# P19_HDMI_OUT.net
KiCad netlist of a schematic drawn in Altium Designer
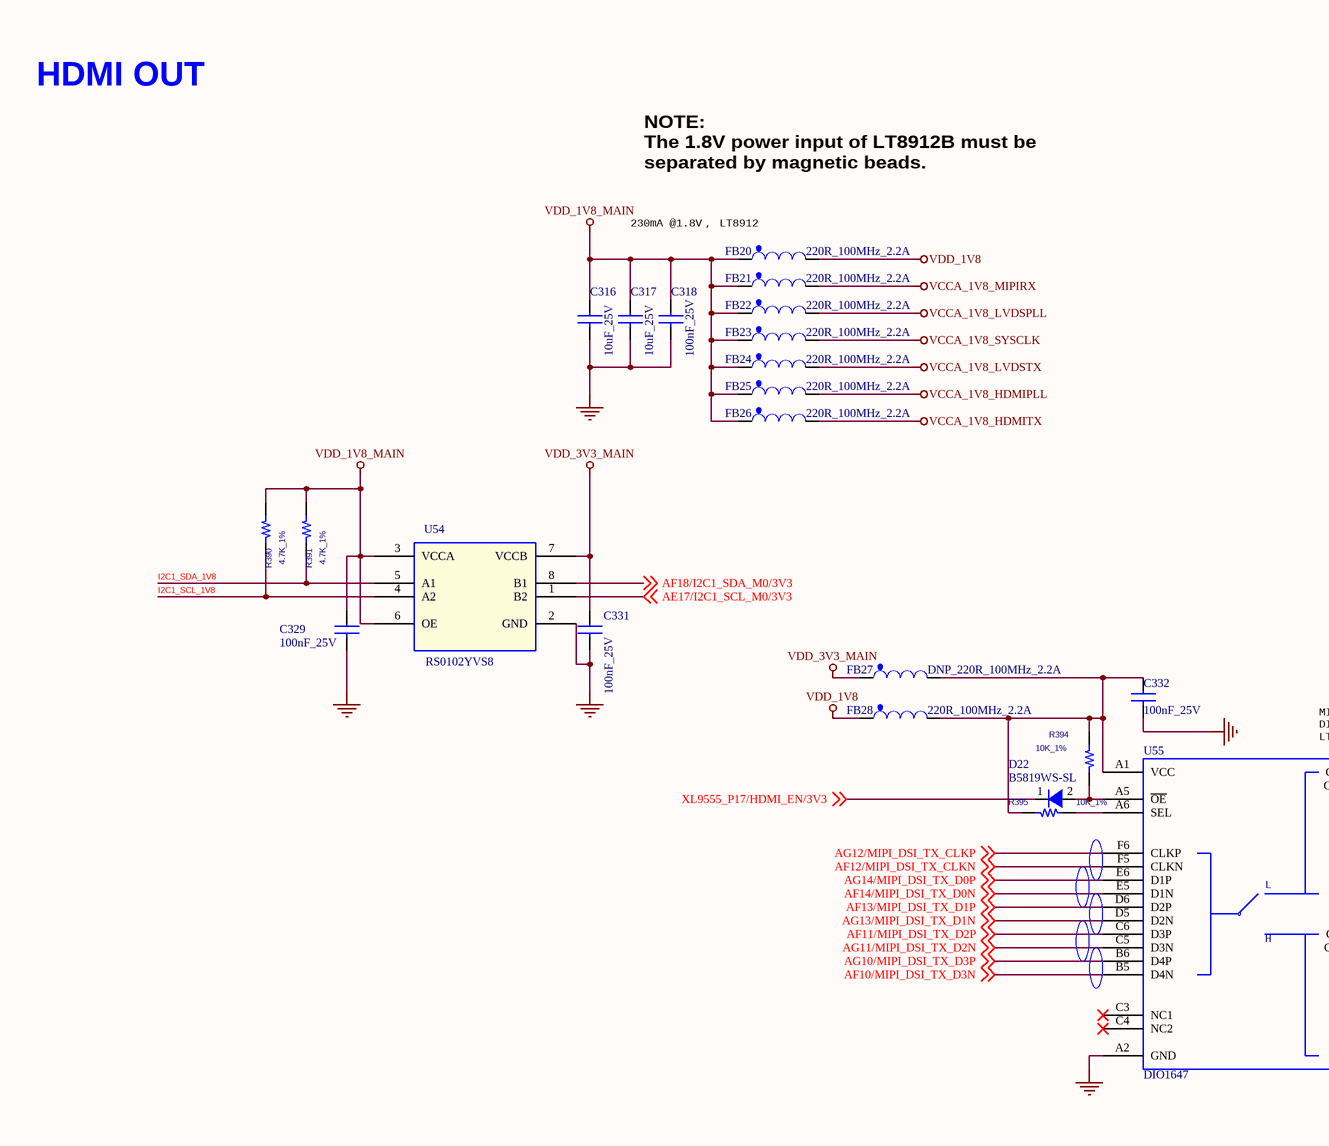
[diagram p0: P19_HDMI OUT.SchDoc, top left]
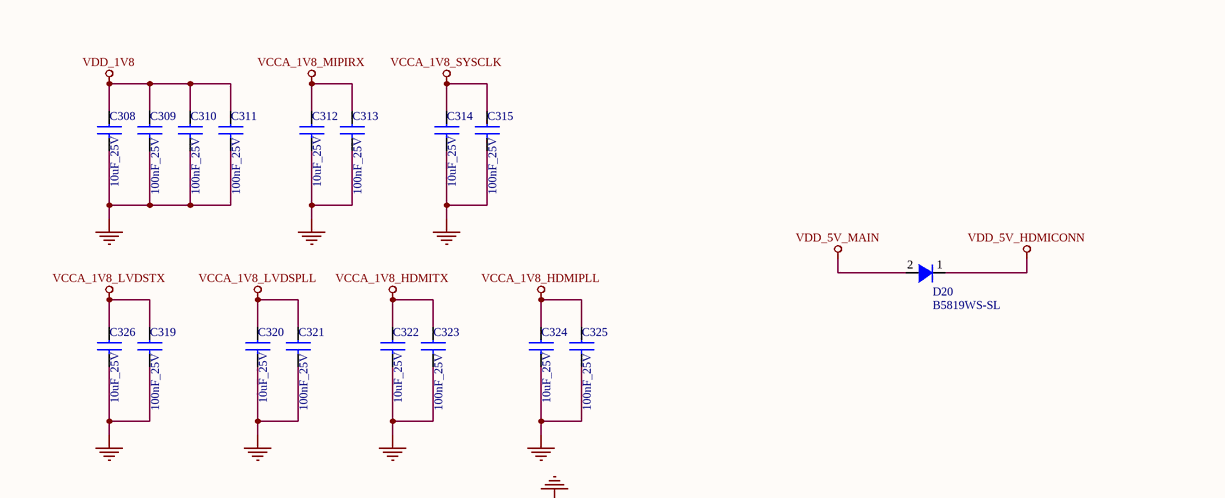
[diagram p1: P19_HDMI OUT.SchDoc, top right]
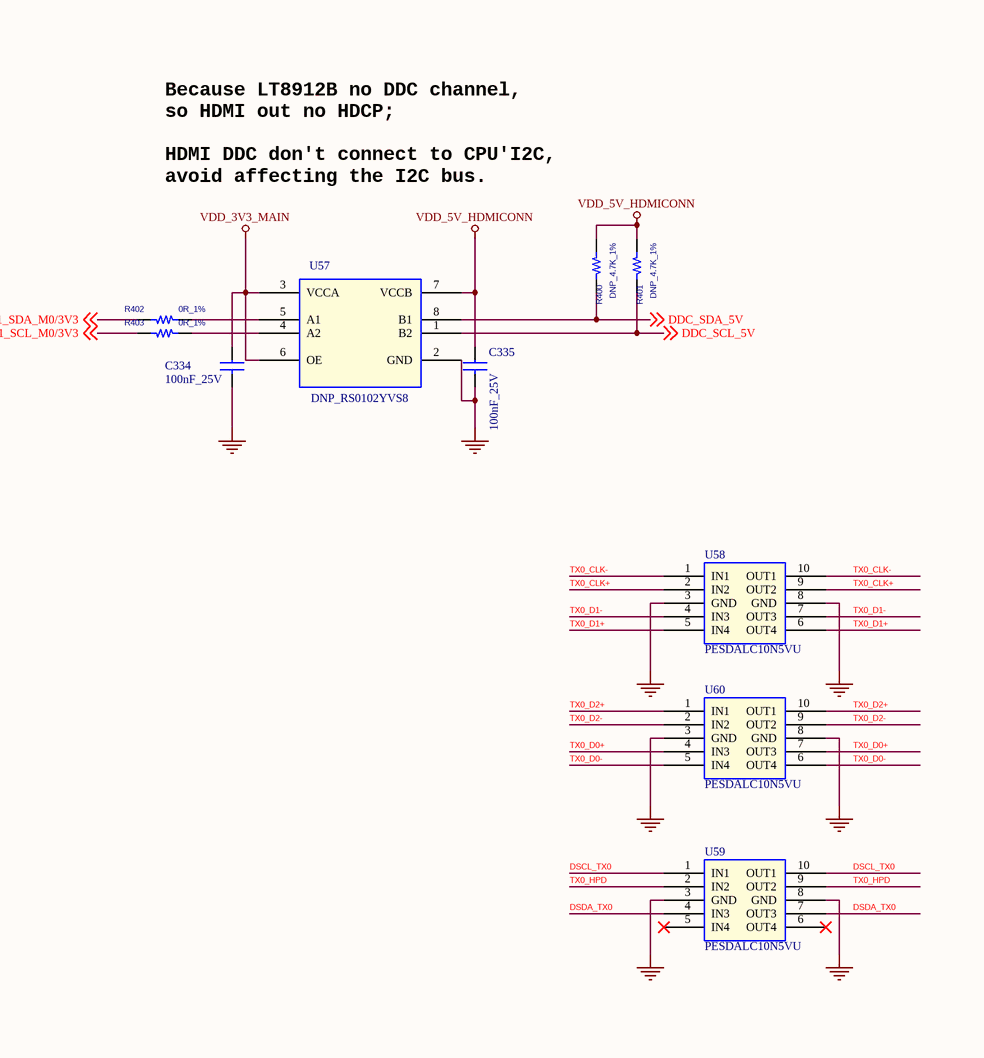
[diagram p2: P19_HDMI OUT.SchDoc, bottom left]
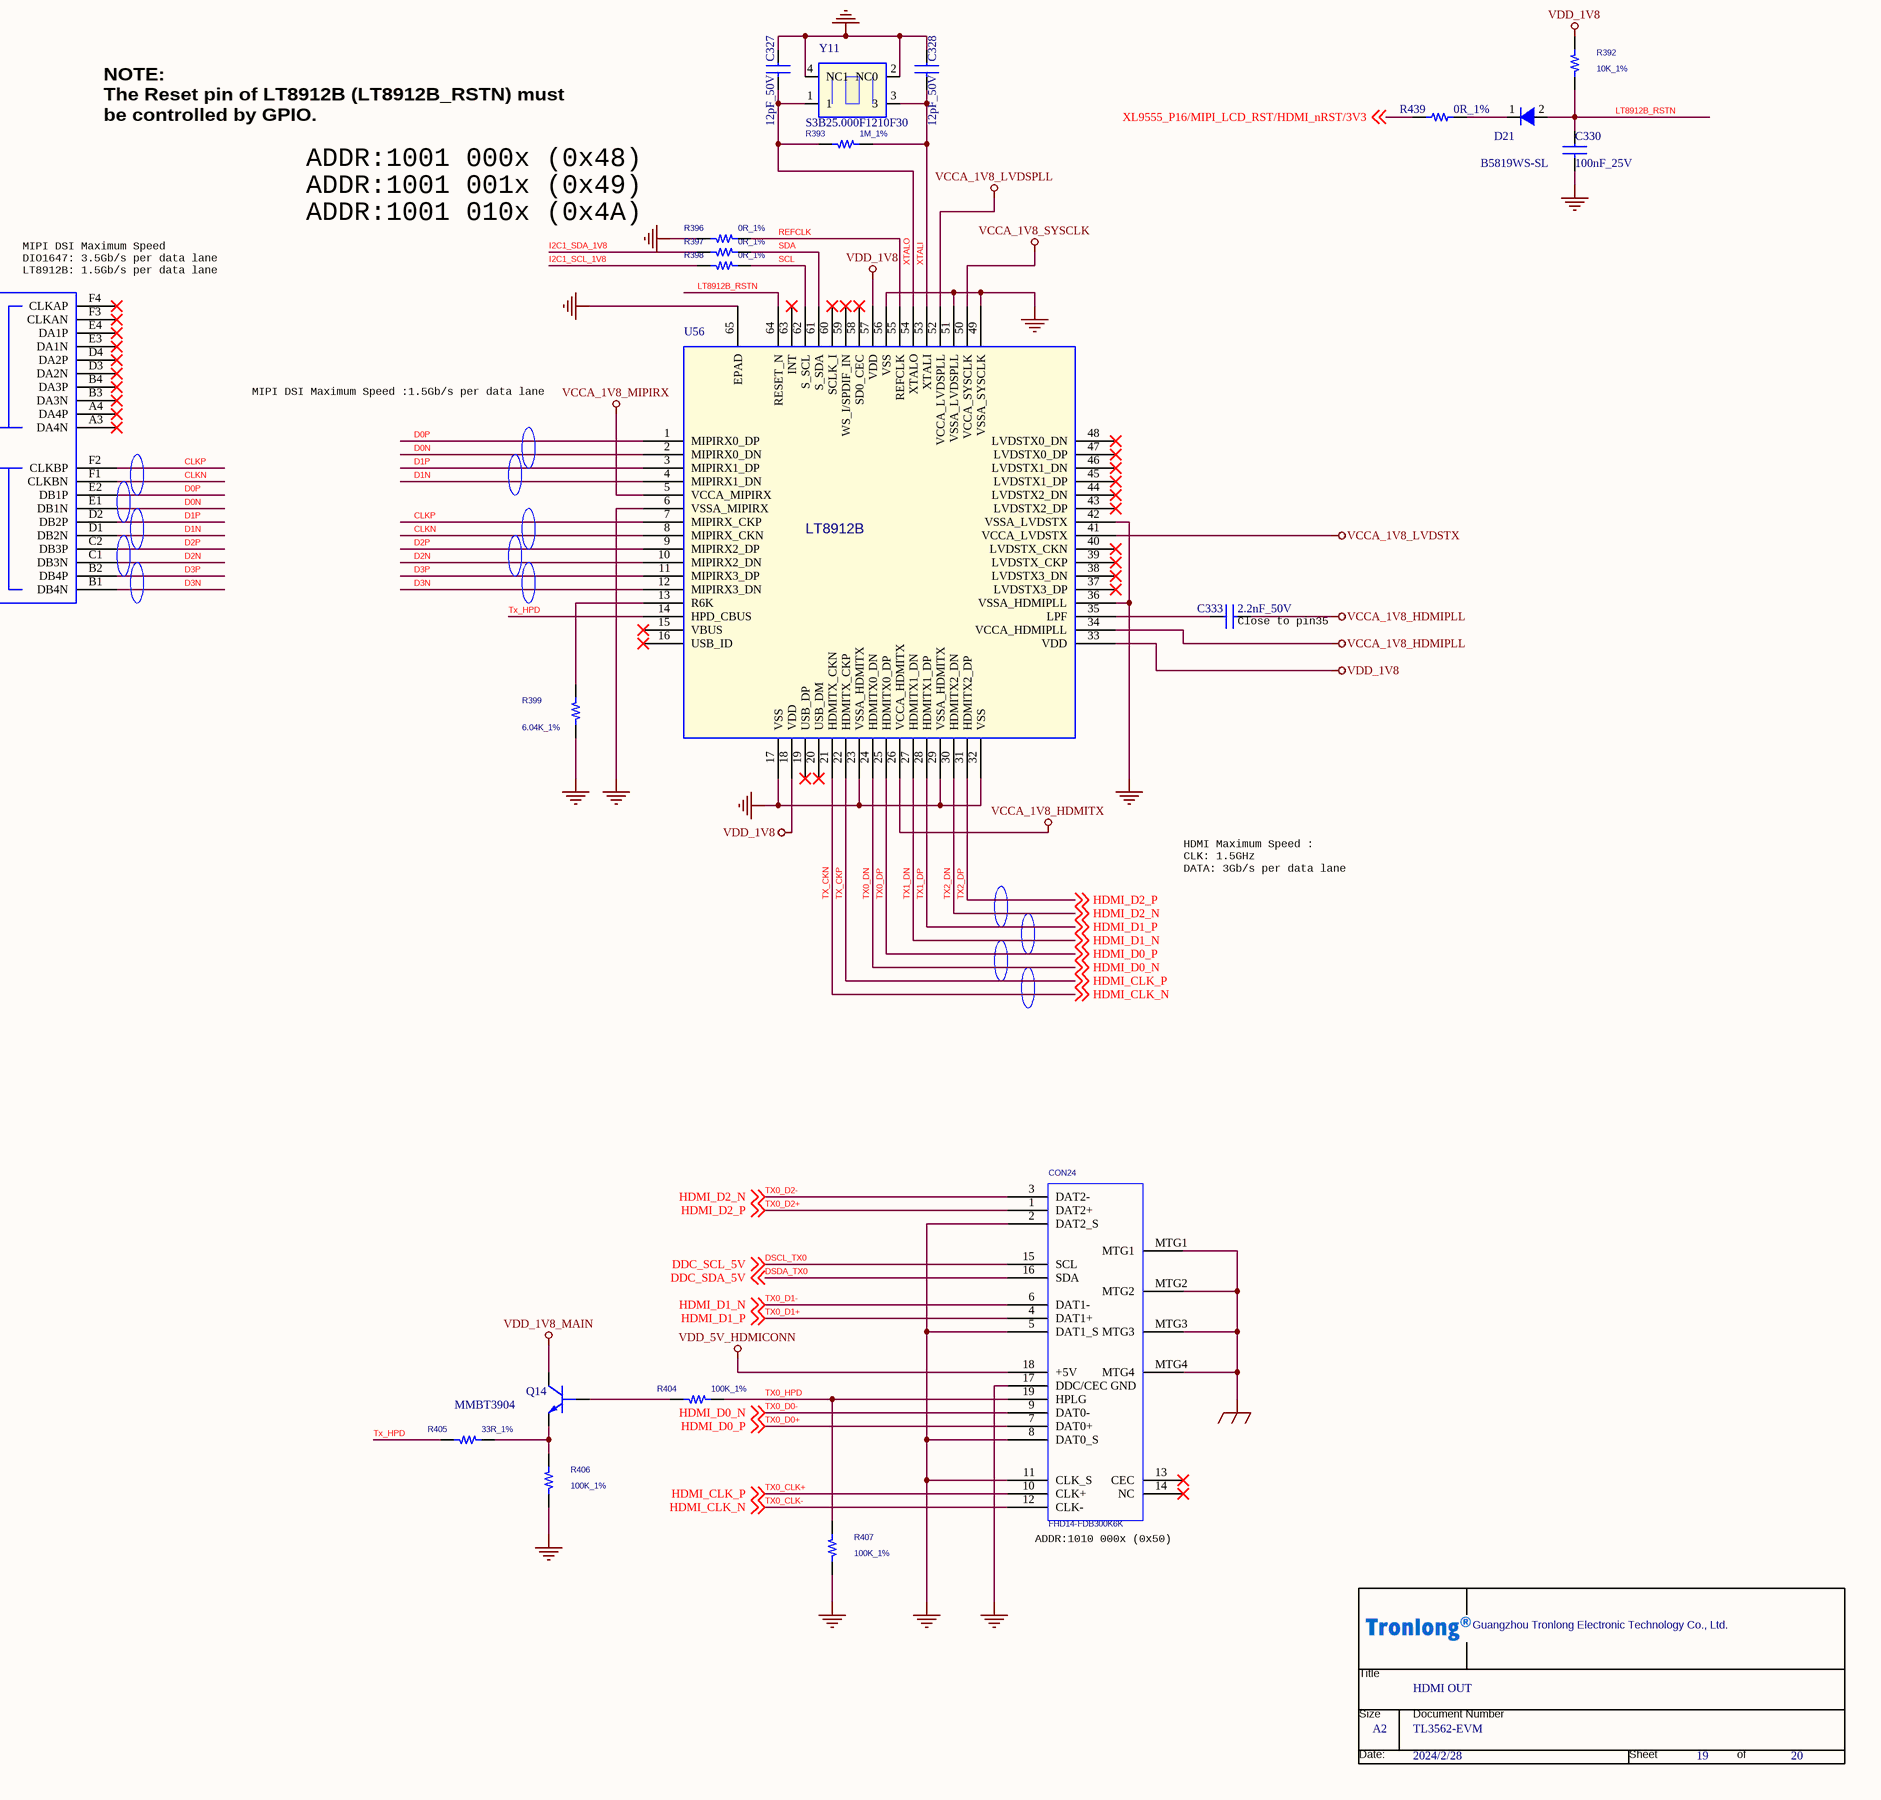
[diagram p3: P19_HDMI OUT.SchDoc, bottom right]

(export (version "E")
  (design (tool "Eeschema 10.0.6"))
  (components
    (comp (ref "C308")
      (value "10uF_25V")
      (footprint "C0603")
      (description "贴片陶瓷电容,10uF,10%,10V,X5R")
      (fields (field (name "PART NUMBER") "117-00-3043") (field (name "DESIGNER") "Hujin"))
      (libsource (lib "*") (part "CAP_NP0603"))
    )
    (comp (ref "C309")
      (value "100nF_25V")
      (footprint "C0402")
      (description "贴片陶瓷电容,100nF,10%,25V,X5R")
      (fields (field (name "PART NUMBER") "117-00-3036") (field (name "DESIGNER") "Hujin"))
      (libsource (lib "*") (part "CAP_NP0603"))
    )
    (comp (ref "C310")
      (value "100nF_25V")
      (footprint "C0402")
      (description "贴片陶瓷电容,100nF,10%,25V,X5R")
      (fields (field (name "PART NUMBER") "117-00-3036") (field (name "DESIGNER") "Hujin"))
      (libsource (lib "*") (part "CAP_NP0603"))
    )
    (comp (ref "C311")
      (value "100nF_25V")
      (footprint "C0402")
      (description "贴片陶瓷电容,100nF,10%,25V,X5R")
      (fields (field (name "PART NUMBER") "117-00-3036") (field (name "DESIGNER") "Hujin"))
      (libsource (lib "*") (part "CAP_NP0603"))
    )
    (comp (ref "C312")
      (value "10uF_25V")
      (footprint "C0603")
      (description "贴片陶瓷电容,10uF,10%,10V,X5R")
      (fields (field (name "PART NUMBER") "117-00-3043") (field (name "DESIGNER") "Hujin"))
      (libsource (lib "*") (part "CAP_NP0603"))
    )
    (comp (ref "C313")
      (value "100nF_25V")
      (footprint "C0402")
      (description "贴片陶瓷电容,100nF,10%,25V,X5R")
      (fields (field (name "PART NUMBER") "117-00-3036") (field (name "DESIGNER") "Hujin"))
      (libsource (lib "*") (part "CAP_NP0603"))
    )
    (comp (ref "C314")
      (value "10uF_25V")
      (footprint "C0603")
      (description "贴片陶瓷电容,10uF,10%,10V,X5R")
      (fields (field (name "PART NUMBER") "117-00-3043") (field (name "DESIGNER") "Hujin"))
      (libsource (lib "*") (part "CAP_NP0603"))
    )
    (comp (ref "C315")
      (value "100nF_25V")
      (footprint "C0402")
      (description "贴片陶瓷电容,100nF,10%,25V,X5R")
      (fields (field (name "PART NUMBER") "117-00-3036") (field (name "DESIGNER") "Hujin"))
      (libsource (lib "*") (part "CAP_NP0603"))
    )
    (comp (ref "C316")
      (value "10uF_25V")
      (footprint "C0603")
      (description "贴片陶瓷电容,10uF,10%,10V,X5R")
      (fields (field (name "PART NUMBER") "117-00-3043") (field (name "DESIGNER") "Hujin"))
      (libsource (lib "*") (part "CAP_NP0603"))
    )
    (comp (ref "C317")
      (value "10uF_25V")
      (footprint "C0603")
      (description "贴片陶瓷电容,10uF,10%,10V,X5R")
      (fields (field (name "PART NUMBER") "117-00-3043") (field (name "DESIGNER") "Hujin"))
      (libsource (lib "*") (part "CAP_NP0603"))
    )
    (comp (ref "C318")
      (value "100nF_25V")
      (footprint "C0402")
      (description "贴片陶瓷电容,100nF,10%,25V,X5R")
      (fields (field (name "PART NUMBER") "117-00-3036") (field (name "DESIGNER") "Hujin"))
      (libsource (lib "*") (part "CAP_NP0603"))
    )
    (comp (ref "C319")
      (value "100nF_25V")
      (footprint "C0402")
      (description "贴片陶瓷电容,100nF,10%,25V,X5R")
      (fields (field (name "PART NUMBER") "117-00-3036") (field (name "DESIGNER") "Hujin"))
      (libsource (lib "*") (part "CAP_NP0603"))
    )
    (comp (ref "C320")
      (value "10uF_25V")
      (footprint "C0603")
      (description "贴片陶瓷电容,10uF,10%,10V,X5R")
      (fields (field (name "PART NUMBER") "117-00-3043") (field (name "DESIGNER") "Hujin"))
      (libsource (lib "*") (part "CAP_NP0603"))
    )
    (comp (ref "C321")
      (value "100nF_25V")
      (footprint "C0402")
      (description "贴片陶瓷电容,100nF,10%,25V,X5R")
      (fields (field (name "PART NUMBER") "117-00-3036") (field (name "DESIGNER") "Hujin"))
      (libsource (lib "*") (part "CAP_NP0603"))
    )
    (comp (ref "C322")
      (value "10uF_25V")
      (footprint "C0603")
      (description "贴片陶瓷电容,10uF,10%,10V,X5R")
      (fields (field (name "PART NUMBER") "117-00-3043") (field (name "DESIGNER") "Hujin"))
      (libsource (lib "*") (part "CAP_NP0603"))
    )
    (comp (ref "C323")
      (value "100nF_25V")
      (footprint "C0402")
      (description "贴片陶瓷电容,100nF,10%,25V,X5R")
      (fields (field (name "PART NUMBER") "117-00-3036") (field (name "DESIGNER") "Hujin"))
      (libsource (lib "*") (part "CAP_NP0603"))
    )
    (comp (ref "C324")
      (value "10uF_25V")
      (footprint "C0603")
      (description "贴片陶瓷电容,10uF,10%,10V,X5R")
      (fields (field (name "PART NUMBER") "117-00-3043") (field (name "DESIGNER") "Hujin"))
      (libsource (lib "*") (part "CAP_NP0603"))
    )
    (comp (ref "C325")
      (value "100nF_25V")
      (footprint "C0402")
      (description "贴片陶瓷电容,100nF,10%,25V,X5R")
      (fields (field (name "PART NUMBER") "117-00-3036") (field (name "DESIGNER") "Hujin"))
      (libsource (lib "*") (part "CAP_NP0603"))
    )
    (comp (ref "C326")
      (value "10uF_25V")
      (footprint "C0603")
      (description "贴片陶瓷电容,10uF,10%,10V,X5R")
      (fields (field (name "PART NUMBER") "117-00-3043") (field (name "DESIGNER") "Hujin"))
      (libsource (lib "*") (part "CAP_NP0603"))
    )
    (comp (ref "C327")
      (value "12pF_50V")
      (footprint "C0402")
      (description "贴片陶瓷电容,12pF,5%,50V,COG")
      (fields (field (name "PART NUMBER") "117-00-3002") (field (name "DESIGNER") "Hujin"))
      (libsource (lib "*") (part "CAP_NP0603"))
    )
    (comp (ref "C328")
      (value "12pF_50V")
      (footprint "C0402")
      (description "贴片陶瓷电容,12pF,5%,50V,COG")
      (fields (field (name "PART NUMBER") "117-00-3002") (field (name "DESIGNER") "Hujin"))
      (libsource (lib "*") (part "CAP_NP0603"))
    )
    (comp (ref "C329")
      (value "100nF_25V")
      (footprint "C0402")
      (description "贴片陶瓷电容,100nF,10%,25V,X5R")
      (libsource (lib "*") (part "CAP NP_Dup3"))
    )
    (comp (ref "C330")
      (value "100nF_25V")
      (footprint "C0402")
      (description "贴片陶瓷电容,100nF,10%,25V,X5R")
      (fields (field (name "PART NUMBER") "117-00-3036") (field (name "DESIGNER") "Hujin"))
      (libsource (lib "*") (part "CAP_NP0603"))
    )
    (comp (ref "C331")
      (value "100nF_25V")
      (footprint "C0402")
      (description "贴片陶瓷电容,100nF,10%,25V,X5R")
      (libsource (lib "*") (part "CAP NP_Dup3"))
    )
    (comp (ref "C332")
      (value "100nF_25V")
      (footprint "C0402")
      (description "贴片陶瓷电容,100nF,10%,25V,X5R")
      (fields (field (name "PART NUMBER") "117-00-3036"))
      (libsource (lib "*") (part "CAP_NP"))
    )
    (comp (ref "C333")
      (value "2.2nF_50V")
      (footprint "C0603")
      (description "2.2nF,10%,C0603,50V,")
      (fields (field (name "PART NUMBER") "117-00-3023") (field (name "DESIGNER") "Hujin"))
      (libsource (lib "*") (part "CAP_NP0603"))
    )
    (comp (ref "C334")
      (value "100nF_25V")
      (footprint "C0402")
      (description "贴片陶瓷电容,100nF,10%,25V,X5R")
      (libsource (lib "*") (part "CAP NP_Dup3"))
    )
    (comp (ref "C335")
      (value "100nF_25V")
      (footprint "C0402")
      (description "贴片陶瓷电容,100nF,10%,25V,X5R")
      (libsource (lib "*") (part "CAP NP_Dup3"))
    )
    (comp (ref "CON24")
      (value "FHD14-FDB300K6K")
      (footprint "DIP_HDMI-A")
      (description "HDMI接口，19PIN，侧立，90度")
      (fields (field (name "MFR") "FCI") (field (name "TIINTPARTNUMBER") "2C0085"))
      (libsource (lib "TL3562-EVM-A1-0-000-D-20231116") (part "2C_Conn_HDMI_TypeA"))
    )
    (comp (ref "D20")
      (value "B5819WS-SL")
      (footprint "SOD-323")
      (description "肖特基二极管,VR=40V,IF=1A,VF=0.6V@1A")
      (fields (field (name "TIINTPARTNUMBER") "1E0013") (field (name "MFR") "On Semiconductor"))
      (libsource (lib "*") (part "Diode200mA250V_2"))
    )
    (comp (ref "D21")
      (value "B5819WS-SL")
      (footprint "SOD-323")
      (description "肖特基二极管,VR=40V,IF=1A,VF=0.6V@1A")
      (fields (field (name "TIINTPARTNUMBER") "1E0013") (field (name "MFR") "On Semiconductor"))
      (libsource (lib "*") (part "Diode200mA250V_2"))
    )
    (comp (ref "D22")
      (value "B5819WS-SL")
      (footprint "SOD-323")
      (description "肖特基二极管,VR=40V,IF=1A,VF=0.6V@1A")
      (fields (field (name "TIINTPARTNUMBER") "1E0013") (field (name "MFR") "On Semiconductor"))
      (libsource (lib "*") (part "Diode200mA250V_2"))
    )
    (comp (ref "FB20")
      (value "220R_100MHz_2.2A")
      (footprint "L0603")
      (description "磁珠,50mΩ,2.2A,220R@100MHz")
      (fields
        (field (name "MANUFACTURER") "深圳顺络电子股份有限公司（Sunlord）")
        (field (name "MANUFACTURER PARTNUMBER") "UPZ1608U221-2R2TF")
      )
      (libsource (lib "*") (part "FERRITE BEAD"))
    )
    (comp (ref "FB21")
      (value "220R_100MHz_2.2A")
      (footprint "L0603")
      (description "磁珠,50mΩ,2.2A,220R@100MHz")
      (fields
        (field (name "MANUFACTURER") "深圳顺络电子股份有限公司（Sunlord）")
        (field (name "MANUFACTURER PARTNUMBER") "UPZ1608U221-2R2TF")
      )
      (libsource (lib "*") (part "FERRITE BEAD"))
    )
    (comp (ref "FB22")
      (value "220R_100MHz_2.2A")
      (footprint "L0603")
      (description "磁珠,50mΩ,2.2A,220R@100MHz")
      (fields
        (field (name "MANUFACTURER") "深圳顺络电子股份有限公司（Sunlord）")
        (field (name "MANUFACTURER PARTNUMBER") "UPZ1608U221-2R2TF")
      )
      (libsource (lib "*") (part "FERRITE BEAD"))
    )
    (comp (ref "FB23")
      (value "220R_100MHz_2.2A")
      (footprint "L0603")
      (description "磁珠,50mΩ,2.2A,220R@100MHz")
      (fields
        (field (name "MANUFACTURER") "深圳顺络电子股份有限公司（Sunlord）")
        (field (name "MANUFACTURER PARTNUMBER") "UPZ1608U221-2R2TF")
      )
      (libsource (lib "*") (part "FERRITE BEAD"))
    )
    (comp (ref "FB24")
      (value "220R_100MHz_2.2A")
      (footprint "L0603")
      (description "磁珠,50mΩ,2.2A,220R@100MHz")
      (fields
        (field (name "MANUFACTURER") "深圳顺络电子股份有限公司（Sunlord）")
        (field (name "MANUFACTURER PARTNUMBER") "UPZ1608U221-2R2TF")
      )
      (libsource (lib "*") (part "FERRITE BEAD"))
    )
    (comp (ref "FB25")
      (value "220R_100MHz_2.2A")
      (footprint "L0603")
      (description "磁珠,50mΩ,2.2A,220R@100MHz")
      (fields
        (field (name "MANUFACTURER") "深圳顺络电子股份有限公司（Sunlord）")
        (field (name "MANUFACTURER PARTNUMBER") "UPZ1608U221-2R2TF")
      )
      (libsource (lib "*") (part "FERRITE BEAD"))
    )
    (comp (ref "FB26")
      (value "220R_100MHz_2.2A")
      (footprint "L0603")
      (description "磁珠,50mΩ,2.2A,220R@100MHz")
      (fields
        (field (name "MANUFACTURER") "深圳顺络电子股份有限公司（Sunlord）")
        (field (name "MANUFACTURER PARTNUMBER") "UPZ1608U221-2R2TF")
      )
      (libsource (lib "*") (part "FERRITE BEAD"))
    )
    (comp (ref "FB27")
      (value "DNP_220R_100MHz_2.2A")
      (footprint "L0603")
      (description "磁珠,50mΩ,2.2A,220R@100MHz")
      (fields
        (field (name "PART NUMBER") "647-01-3069")
        (field (name "MANUFACTURER PARTNUMBER") "UPZ1608U221-2R2TF")
      )
      (libsource (lib "*") (part "FERRITE BEAD"))
    )
    (comp (ref "FB28")
      (value "220R_100MHz_2.2A")
      (footprint "L0603")
      (description "磁珠,50mΩ,2.2A,220R@100MHz")
      (fields
        (field (name "PART NUMBER") "647-01-3069")
        (field (name "MANUFACTURER PARTNUMBER") "UPZ1608U221-2R2TF")
      )
      (libsource (lib "*") (part "FERRITE BEAD"))
    )
    (comp (ref "Q14")
      (value "MMBT3904")
      (footprint "SOT23-3_DBZ3")
      (description "BJT,NPN,Vceo=40V,Ic=200mA,fT=300MHz,PD=200mW")
      (fields (field (name "MANUFACTURER") "江苏长晶科技有限公司（JSCJ）"))
      (libsource (lib "*") (part "MMBT3904/SOT"))
    )
    (comp (ref "R390")
      (value "4.7K_1%")
      (footprint "R0402")
      (description "贴片电阻,4.7K,±1%,1/16W")
      (libsource (lib "*") (part "Resistor_Dup3"))
    )
    (comp (ref "R391")
      (value "4.7K_1%")
      (footprint "R0402")
      (description "贴片电阻,4.7K,±1%,1/16W")
      (libsource (lib "*") (part "Resistor_Dup3"))
    )
    (comp (ref "R392")
      (value "10K_1%")
      (footprint "R0402")
      (description "贴片电阻,10K,±1%,1/16W")
      (libsource (lib "*") (part "Resistor_Dup3"))
    )
    (comp (ref "R393")
      (value "1M_1%")
      (footprint "R0603")
      (description "贴片电阻,1M,±1%,1/10W")
      (libsource (lib "*") (part "Resistor_Dup3"))
    )
    (comp (ref "R394")
      (value "10K_1%")
      (footprint "R0402")
      (description "贴片电阻,10K,±1%,1/16W")
      (libsource (lib "*") (part "10_R_0"))
    )
    (comp (ref "R395")
      (value "10K_1%")
      (footprint "R0402")
      (description "贴片电阻,10K,±1%,1/16W")
      (libsource (lib "*") (part "10_R_0"))
    )
    (comp (ref "R396")
      (value "0R_1%")
      (footprint "R0402")
      (description "0R,±1%,R0402,≥1/16W")
      (libsource (lib "*") (part "Resistor_Dup3"))
    )
    (comp (ref "R397")
      (value "0R_1%")
      (footprint "R0402")
      (description "0R,±1%,R0402,≥1/16W")
      (libsource (lib "*") (part "Resistor_Dup3"))
    )
    (comp (ref "R398")
      (value "0R_1%")
      (footprint "R0402")
      (description "0R,±1%,R0402,≥1/16W")
      (libsource (lib "*") (part "Resistor_Dup3"))
    )
    (comp (ref "R399")
      (value "6.04K_1%")
      (footprint "R0402")
      (description "贴片电阻,6.04K,±1%,1/16W")
      (libsource (lib "*") (part "Resistor_Dup3"))
    )
    (comp (ref "R400")
      (value "DNP_4.7K_1%")
      (footprint "R0402")
      (description "贴片电阻,4.7K,±1%,1/16W")
      (libsource (lib "*") (part "Resistor_Dup3"))
    )
    (comp (ref "R401")
      (value "DNP_4.7K_1%")
      (footprint "R0402")
      (description "贴片电阻,4.7K,±1%,1/16W")
      (libsource (lib "*") (part "Resistor_Dup3"))
    )
    (comp (ref "R402")
      (value "0R_1%")
      (footprint "R0402")
      (description "0R,±1%,R0402,≥1/16W")
      (libsource (lib "*") (part "Resistor_Dup3"))
    )
    (comp (ref "R403")
      (value "0R_1%")
      (footprint "R0402")
      (description "0R,±1%,R0402,≥1/16W")
      (libsource (lib "*") (part "Resistor_Dup3"))
    )
    (comp (ref "R404")
      (value "100K_1%")
      (footprint "R0402")
      (description "贴片电阻,100K,±1%,1/16W")
      (libsource (lib "*") (part "Resistor_Dup3"))
    )
    (comp (ref "R405")
      (value "33R_1%")
      (footprint "R0402")
      (description "贴片电阻,33R,±1%,1/16W")
      (libsource (lib "*") (part "Resistor_Dup3"))
    )
    (comp (ref "R406")
      (value "100K_1%")
      (footprint "R0402")
      (description "贴片电阻,100K,±1%,1/16W")
      (libsource (lib "*") (part "Resistor_Dup3"))
    )
    (comp (ref "R407")
      (value "100K_1%")
      (footprint "R0402")
      (description "贴片电阻,100K,±1%,1/16W")
      (libsource (lib "*") (part "Resistor_Dup3"))
    )
    (comp (ref "R439")
      (value "0R_1%")
      (footprint "R0402")
      (description "0R,±1%,R0402,≥1/16W")
      (libsource (lib "*") (part "Resistor_Dup3"))
    )
    (comp (ref "U54")
      (value "RS0102YVS8")
      (footprint "SOP8-20-91")
      (description "2位双向电平转换器")
      (fields (field (name "MANUFACTURER") "江苏润石科技有限公司（RUNIC）"))
      (libsource (lib "*") (part "TXS0102DCUR"))
    )
    (comp (ref "U55")
      (value "DIO1647")
      (footprint "WLCSP-36-0d4mm")
      (description "3.5GHz, 十单刀双掷MIPI 开关")
      (fields
        (field (name "MANUFACTURER PARTNUMBER") "DIO1647WL36")
        (field (name "MANUFACTURER") "江苏帝奥微电子股份有限公司")
      )
      (libsource (lib "TL3562-EVM-A1-0-000-D-20231116") (part "DIO1647_0"))
    )
    (comp (ref "U56")
      (value "LT8912B")
      (footprint "QFN64_LT8912B")
      (description "MIPI转HDMI/LVDS")
      (fields (field (name "MANUFACTURER") "龙迅半导体（合肥）股份有限公司") (field (name "PART NUMBER") "566-00-3037"))
      (libsource (lib "*") (part "LT8912B_QFN64_0"))
    )
    (comp (ref "U57")
      (value "DNP_RS0102YVS8")
      (footprint "SOP8-20-91")
      (description "2位双向电平转换器")
      (fields
        (field (name "MANUFACTURER PARTNUMBER") "RS0102YVS8")
        (field (name "MANUFACTURER") "江苏润石科技有限公司（RUNIC）")
      )
      (libsource (lib "*") (part "TXS0102DCUR"))
    )
    (comp (ref "U58")
      (value "PESDALC10N5VU")
      (footprint "DFN-10-2510")
      (description "4通道超低电容瞬态抑制器")
      (fields (field (name "MANUFACTURER") "上海芯导电子科技有限公司（Prisemi）"))
      (libsource (lib "*") (part "RCLAMP0524P"))
    )
    (comp (ref "U59")
      (value "PESDALC10N5VU")
      (footprint "DFN-10-2510")
      (description "4通道超低电容瞬态抑制器")
      (fields (field (name "MANUFACTURER") "上海芯导电子科技有限公司（Prisemi）"))
      (libsource (lib "*") (part "RCLAMP0524P"))
    )
    (comp (ref "U60")
      (value "PESDALC10N5VU")
      (footprint "DFN-10-2510")
      (description "4通道超低电容瞬态抑制器")
      (fields (field (name "MANUFACTURER") "上海芯导电子科技有限公司（Prisemi）"))
      (libsource (lib "*") (part "RCLAMP0524P"))
    )
    (comp (ref "Y11")
      (value "S3B25.000F1210F30")
      (footprint "SMD_3225")
      (description "四脚无源晶振,25MHz,±10ppm,12pF,30Ω,±30ppm")
      (fields (field (name "MANUFACTURER") "深圳市星通时频电子有限公司公司（JSCJ）"))
      (libsource (lib "*") (part "CRYS-4PIN"))
    )
  )
  (nets
    (net (code "1") (name "/CLKN") (class "Default")
      (node (ref "U55") (pin "F1") (pinfunction "CLKBN_F1") (pintype "passive"))
      (node (ref "U56") (pin "8") (pinfunction "MIPIRX_CKN_8") (pintype "passive"))
    )
    (net (code "2") (name "/CLKP") (class "Default")
      (node (ref "U55") (pin "F2") (pinfunction "CLKBP_F2") (pintype "passive"))
      (node (ref "U56") (pin "7") (pinfunction "MIPIRX_CKP_7") (pintype "passive"))
    )
    (net (code "3") (name "/D0N") (class "Default")
      (node (ref "U55") (pin "E1") (pinfunction "DB1N_E1") (pintype "passive"))
      (node (ref "U56") (pin "2") (pinfunction "MIPIRX0_DN_2") (pintype "passive"))
    )
    (net (code "4") (name "/D0P") (class "Default")
      (node (ref "U55") (pin "E2") (pinfunction "DB1P_E2") (pintype "passive"))
      (node (ref "U56") (pin "1") (pinfunction "MIPIRX0_DP_1") (pintype "passive"))
    )
    (net (code "5") (name "/D1N") (class "Default")
      (node (ref "U55") (pin "D1") (pinfunction "DB2N_D1") (pintype "passive"))
      (node (ref "U56") (pin "4") (pinfunction "MIPIRX1_DN_4") (pintype "passive"))
    )
    (net (code "6") (name "/D1P") (class "Default")
      (node (ref "U55") (pin "D2") (pinfunction "DB2P_D2") (pintype "passive"))
      (node (ref "U56") (pin "3") (pinfunction "MIPIRX1_DP_3") (pintype "passive"))
    )
    (net (code "7") (name "/D2N") (class "Default")
      (node (ref "U55") (pin "C1") (pinfunction "DB3N_C1") (pintype "passive"))
      (node (ref "U56") (pin "10") (pinfunction "MIPIRX2_DN_10") (pintype "passive"))
    )
    (net (code "8") (name "/D2P") (class "Default")
      (node (ref "U55") (pin "C2") (pinfunction "DB3P_C2") (pintype "passive"))
      (node (ref "U56") (pin "9") (pinfunction "MIPIRX2_DP_9") (pintype "passive"))
    )
    (net (code "9") (name "/D3N") (class "Default")
      (node (ref "U55") (pin "B1") (pinfunction "DB4N_B1") (pintype "passive"))
      (node (ref "U56") (pin "12") (pinfunction "MIPIRX3_DN_12") (pintype "passive"))
    )
    (net (code "10") (name "/D3P") (class "Default")
      (node (ref "U55") (pin "B2") (pinfunction "DB4P_B2") (pintype "passive"))
      (node (ref "U56") (pin "11") (pinfunction "MIPIRX3_DP_11") (pintype "passive"))
    )
    (net (code "11") (name "/I2C1_SCL_1V8") (class "Default")
      (node (ref "R390") (pin "1") (pinfunction "1_1") (pintype "passive"))
      (node (ref "R398") (pin "1") (pinfunction "1_1") (pintype "passive"))
      (node (ref "U54") (pin "4") (pinfunction "A2_4") (pintype "passive"))
    )
    (net (code "12") (name "/I2C1_SDA_1V8") (class "Default")
      (node (ref "R391") (pin "1") (pinfunction "1_1") (pintype "passive"))
      (node (ref "R397") (pin "1") (pinfunction "1_1") (pintype "passive"))
      (node (ref "U54") (pin "5") (pinfunction "A1_5") (pintype "passive"))
    )
    (net (code "13") (name "/LT8912B_RSTN") (class "Default")
      (node (ref "C330") (pin "1") (pinfunction "1_1") (pintype "passive"))
      (node (ref "D21") (pin "2") (pinfunction "Cathode_2") (pintype "passive"))
      (node (ref "R392") (pin "1") (pinfunction "1_1") (pintype "passive"))
      (node (ref "U56") (pin "64") (pinfunction "RESET_N_64") (pintype "passive"))
    )
    (net (code "14") (name "/REFCLK") (class "Default")
      (node (ref "R396") (pin "2") (pinfunction "2_2") (pintype "passive"))
      (node (ref "U56") (pin "55") (pinfunction "REFCLK_55") (pintype "passive"))
    )
    (net (code "15") (name "/SCL") (class "Default")
      (node (ref "R398") (pin "2") (pinfunction "2_2") (pintype "passive"))
      (node (ref "U56") (pin "62") (pinfunction "S_SCL_62") (pintype "passive"))
    )
    (net (code "16") (name "/SDA") (class "Default")
      (node (ref "R397") (pin "2") (pinfunction "2_2") (pintype "passive"))
      (node (ref "U56") (pin "61") (pinfunction "S_SDA_61") (pintype "passive"))
    )
    (net (code "17") (name "/TX0_HPD") (class "Default")
      (node (ref "CON24") (pin "19") (pinfunction "HPLG_19") (pintype "passive"))
      (node (ref "R404") (pin "1") (pinfunction "1_1") (pintype "passive"))
      (node (ref "R407") (pin "2") (pinfunction "2_2") (pintype "passive"))
      (node (ref "U59") (pin "2") (pinfunction "IN2_2") (pintype "passive"))
      (node (ref "U59") (pin "9") (pinfunction "OUT2_9") (pintype "passive"))
    )
    (net (code "18") (name "/Tx_HPD") (class "Default")
      (node (ref "R405") (pin "2") (pinfunction "2_2") (pintype "passive"))
      (node (ref "U56") (pin "14") (pinfunction "HPD_CBUS_14") (pintype "passive"))
    )
    (net (code "19") (name "/XTALI") (class "Default")
      (node (ref "C328") (pin "2") (pinfunction "2_2") (pintype "passive"))
      (node (ref "R393") (pin "1") (pinfunction "1_1") (pintype "passive"))
      (node (ref "U56") (pin "53") (pinfunction "XTALI_53") (pintype "passive"))
      (node (ref "Y11") (pin "3") (pinfunction "3_3") (pintype "passive"))
    )
    (net (code "20") (name "/XTALO") (class "Default")
      (node (ref "C327") (pin "2") (pinfunction "2_2") (pintype "passive"))
      (node (ref "R393") (pin "2") (pinfunction "2_2") (pintype "passive"))
      (node (ref "U56") (pin "54") (pinfunction "XTALO_54") (pintype "passive"))
      (node (ref "Y11") (pin "1") (pinfunction "1_1") (pintype "passive"))
    )
    (net (code "21") (name "AE17{slash}I2C1_SCL_M0{slash}3V3") (class "Default")
      (node (ref "R403") (pin "2") (pinfunction "2_2") (pintype "passive"))
      (node (ref "U54") (pin "1") (pinfunction "B2_1") (pintype "passive"))
    )
    (net (code "22") (name "AF10{slash}MIPI_DSI_TX_D3N") (class "Default")
      (node (ref "U55") (pin "B5") (pinfunction "D4N_B5") (pintype "passive"))
    )
    (net (code "23") (name "AF11{slash}MIPI_DSI_TX_D2P") (class "Default")
      (node (ref "U55") (pin "C6") (pinfunction "D3P_C6") (pintype "passive"))
    )
    (net (code "24") (name "AF12{slash}MIPI_DSI_TX_CLKN") (class "Default")
      (node (ref "U55") (pin "F5") (pinfunction "CLKN_F5") (pintype "passive"))
    )
    (net (code "25") (name "AF13{slash}MIPI_DSI_TX_D1P") (class "Default")
      (node (ref "U55") (pin "D6") (pinfunction "D2P_D6") (pintype "passive"))
    )
    (net (code "26") (name "AF14{slash}MIPI_DSI_TX_D0N") (class "Default")
      (node (ref "U55") (pin "E5") (pinfunction "D1N_E5") (pintype "passive"))
    )
    (net (code "27") (name "AF18{slash}I2C1_SDA_M0{slash}3V3") (class "Default")
      (node (ref "R402") (pin "2") (pinfunction "2_2") (pintype "passive"))
      (node (ref "U54") (pin "8") (pinfunction "B1_8") (pintype "passive"))
    )
    (net (code "28") (name "AG10{slash}MIPI_DSI_TX_D3P") (class "Default")
      (node (ref "U55") (pin "B6") (pinfunction "D4P_B6") (pintype "passive"))
    )
    (net (code "29") (name "AG11{slash}MIPI_DSI_TX_D2N") (class "Default")
      (node (ref "U55") (pin "C5") (pinfunction "D3N_C5") (pintype "passive"))
    )
    (net (code "30") (name "AG12{slash}MIPI_DSI_TX_CLKP") (class "Default")
      (node (ref "U55") (pin "F6") (pinfunction "CLKP_F6") (pintype "passive"))
    )
    (net (code "31") (name "AG13{slash}MIPI_DSI_TX_D1N") (class "Default")
      (node (ref "U55") (pin "D5") (pinfunction "D2N_D5") (pintype "passive"))
    )
    (net (code "32") (name "AG14{slash}MIPI_DSI_TX_D0P") (class "Default")
      (node (ref "U55") (pin "E6") (pinfunction "D1P_E6") (pintype "passive"))
    )
    (net (code "33") (name "DDC_SCL_5V") (class "Default")
      (node (ref "CON24") (pin "15") (pinfunction "SCL_15") (pintype "passive"))
      (node (ref "R401") (pin "1") (pinfunction "1_1") (pintype "passive"))
      (node (ref "U57") (pin "1") (pinfunction "B2_1") (pintype "passive"))
      (node (ref "U59") (pin "1") (pinfunction "IN1_1") (pintype "passive"))
      (node (ref "U59") (pin "10") (pinfunction "OUT1_10") (pintype "passive"))
    )
    (net (code "34") (name "DDC_SDA_5V") (class "Default")
      (node (ref "CON24") (pin "16") (pinfunction "SDA_16") (pintype "passive"))
      (node (ref "R400") (pin "1") (pinfunction "1_1") (pintype "passive"))
      (node (ref "U57") (pin "8") (pinfunction "B1_8") (pintype "passive"))
      (node (ref "U59") (pin "4") (pinfunction "IN3_4") (pintype "passive"))
      (node (ref "U59") (pin "7") (pinfunction "OUT3_7") (pintype "passive"))
    )
    (net (code "35") (name "EGND") (class "Default")
      (node (ref "CON24") (pin "MTG1") (pinfunction "MTG1_MTG1") (pintype "power_in"))
      (node (ref "CON24") (pin "MTG2") (pinfunction "MTG2_MTG2") (pintype "power_in"))
      (node (ref "CON24") (pin "MTG3") (pinfunction "MTG3_MTG3") (pintype "power_in"))
      (node (ref "CON24") (pin "MTG4") (pinfunction "MTG4_MTG4") (pintype "power_in"))
    )
    (net (code "36") (name "GND") (class "Default")
      (node (ref "C308") (pin "2") (pinfunction "2_2") (pintype "passive"))
      (node (ref "C309") (pin "2") (pinfunction "2_2") (pintype "passive"))
      (node (ref "C310") (pin "2") (pinfunction "2_2") (pintype "passive"))
      (node (ref "C311") (pin "2") (pinfunction "2_2") (pintype "passive"))
      (node (ref "C312") (pin "2") (pinfunction "2_2") (pintype "passive"))
      (node (ref "C313") (pin "2") (pinfunction "2_2") (pintype "passive"))
      (node (ref "C314") (pin "2") (pinfunction "2_2") (pintype "passive"))
      (node (ref "C315") (pin "2") (pinfunction "2_2") (pintype "passive"))
      (node (ref "C316") (pin "2") (pinfunction "2_2") (pintype "passive"))
      (node (ref "C317") (pin "2") (pinfunction "2_2") (pintype "passive"))
      (node (ref "C318") (pin "2") (pinfunction "2_2") (pintype "passive"))
      (node (ref "C319") (pin "2") (pinfunction "2_2") (pintype "passive"))
      (node (ref "C320") (pin "2") (pinfunction "2_2") (pintype "passive"))
      (node (ref "C321") (pin "2") (pinfunction "2_2") (pintype "passive"))
      (node (ref "C322") (pin "2") (pinfunction "2_2") (pintype "passive"))
      (node (ref "C323") (pin "2") (pinfunction "2_2") (pintype "passive"))
      (node (ref "C324") (pin "2") (pinfunction "2_2") (pintype "passive"))
      (node (ref "C325") (pin "2") (pinfunction "2_2") (pintype "passive"))
      (node (ref "C326") (pin "2") (pinfunction "2_2") (pintype "passive"))
      (node (ref "C327") (pin "1") (pinfunction "1_1") (pintype "passive"))
      (node (ref "C328") (pin "1") (pinfunction "1_1") (pintype "passive"))
      (node (ref "C329") (pin "2") (pinfunction "2_2") (pintype "passive"))
      (node (ref "C330") (pin "2") (pinfunction "2_2") (pintype "passive"))
      (node (ref "C331") (pin "2") (pinfunction "2_2") (pintype "passive"))
      (node (ref "C332") (pin "2") (pinfunction "2_2") (pintype "passive"))
      (node (ref "C334") (pin "2") (pinfunction "2_2") (pintype "passive"))
      (node (ref "C335") (pin "2") (pinfunction "2_2") (pintype "passive"))
      (node (ref "CON24") (pin "11") (pinfunction "CLK_S_11") (pintype "passive"))
      (node (ref "CON24") (pin "17") (pinfunction "DDC/CEC_GND_17") (pintype "passive"))
      (node (ref "CON24") (pin "2") (pinfunction "DAT2_S_2") (pintype "passive"))
      (node (ref "CON24") (pin "5") (pinfunction "DAT1_S_5") (pintype "passive"))
      (node (ref "CON24") (pin "8") (pinfunction "DAT0_S_8") (pintype "passive"))
      (node (ref "R396") (pin "1") (pinfunction "1_1") (pintype "passive"))
      (node (ref "R399") (pin "1") (pinfunction "1_1") (pintype "passive"))
      (node (ref "R406") (pin "1") (pinfunction "1_1") (pintype "passive"))
      (node (ref "R407") (pin "1") (pinfunction "1_1") (pintype "passive"))
      (node (ref "U54") (pin "2") (pinfunction "GND_2") (pintype "passive"))
      (node (ref "U55") (pin "A2") (pinfunction "GND_A2") (pintype "power_in"))
      (node (ref "U56") (pin "17") (pinfunction "VSS_17") (pintype "power_in"))
      (node (ref "U56") (pin "23") (pinfunction "VSSA_HDMITX_23") (pintype "power_in"))
      (node (ref "U56") (pin "29") (pinfunction "VSSA_HDMITX_29") (pintype "power_in"))
      (node (ref "U56") (pin "32") (pinfunction "VSS_32") (pintype "power_in"))
      (node (ref "U56") (pin "36") (pinfunction "VSSA_HDMIPLL_36") (pintype "power_in"))
      (node (ref "U56") (pin "42") (pinfunction "VSSA_LVDSTX_42") (pintype "power_in"))
      (node (ref "U56") (pin "49") (pinfunction "VSSA_SYSCLK_49") (pintype "power_in"))
      (node (ref "U56") (pin "51") (pinfunction "VSSA_LVDSPLL_51") (pintype "power_in"))
      (node (ref "U56") (pin "56") (pinfunction "VSS_56") (pintype "power_in"))
      (node (ref "U56") (pin "6") (pinfunction "VSSA_MIPIRX_6") (pintype "power_in"))
      (node (ref "U56") (pin "65") (pinfunction "EPAD_65") (pintype "passive"))
      (node (ref "U57") (pin "2") (pinfunction "GND_2") (pintype "passive"))
      (node (ref "U58") (pin "3") (pinfunction "GND_3") (pintype "power_in"))
      (node (ref "U58") (pin "8") (pinfunction "GND_8") (pintype "power_in"))
      (node (ref "U59") (pin "3") (pinfunction "GND_3") (pintype "power_in"))
      (node (ref "U59") (pin "8") (pinfunction "GND_8") (pintype "power_in"))
      (node (ref "U60") (pin "3") (pinfunction "GND_3") (pintype "power_in"))
      (node (ref "U60") (pin "8") (pinfunction "GND_8") (pintype "power_in"))
      (node (ref "Y11") (pin "2") (pinfunction "NC0_2") (pintype "passive"))
      (node (ref "Y11") (pin "4") (pinfunction "NC1_4") (pintype "passive"))
    )
    (net (code "37") (name "HDMI_CLK_N") (class "Default")
      (node (ref "CON24") (pin "12") (pinfunction "CLK-_12") (pintype "passive"))
      (node (ref "U56") (pin "21") (pinfunction "HDMITX_CKN_21") (pintype "passive"))
      (node (ref "U58") (pin "1") (pinfunction "IN1_1") (pintype "passive"))
      (node (ref "U58") (pin "10") (pinfunction "OUT1_10") (pintype "passive"))
    )
    (net (code "38") (name "HDMI_CLK_P") (class "Default")
      (node (ref "CON24") (pin "10") (pinfunction "CLK+_10") (pintype "passive"))
      (node (ref "U56") (pin "22") (pinfunction "HDMITX_CKP_22") (pintype "passive"))
      (node (ref "U58") (pin "2") (pinfunction "IN2_2") (pintype "passive"))
      (node (ref "U58") (pin "9") (pinfunction "OUT2_9") (pintype "passive"))
    )
    (net (code "39") (name "HDMI_D0_N") (class "Default")
      (node (ref "CON24") (pin "9") (pinfunction "DAT0-_9") (pintype "passive"))
      (node (ref "U56") (pin "24") (pinfunction "HDMITX0_DN_24") (pintype "passive"))
      (node (ref "U60") (pin "5") (pinfunction "IN4_5") (pintype "passive"))
      (node (ref "U60") (pin "6") (pinfunction "OUT4_6") (pintype "passive"))
    )
    (net (code "40") (name "HDMI_D0_P") (class "Default")
      (node (ref "CON24") (pin "7") (pinfunction "DAT0+_7") (pintype "passive"))
      (node (ref "U56") (pin "25") (pinfunction "HDMITX0_DP_25") (pintype "passive"))
      (node (ref "U60") (pin "4") (pinfunction "IN3_4") (pintype "passive"))
      (node (ref "U60") (pin "7") (pinfunction "OUT3_7") (pintype "passive"))
    )
    (net (code "41") (name "HDMI_D1_N") (class "Default")
      (node (ref "CON24") (pin "6") (pinfunction "DAT1-_6") (pintype "passive"))
      (node (ref "U56") (pin "27") (pinfunction "HDMITX1_DN_27") (pintype "passive"))
      (node (ref "U58") (pin "4") (pinfunction "IN3_4") (pintype "passive"))
      (node (ref "U58") (pin "7") (pinfunction "OUT3_7") (pintype "passive"))
    )
    (net (code "42") (name "HDMI_D1_P") (class "Default")
      (node (ref "CON24") (pin "4") (pinfunction "DAT1+_4") (pintype "passive"))
      (node (ref "U56") (pin "28") (pinfunction "HDMITX1_DP_28") (pintype "passive"))
      (node (ref "U58") (pin "5") (pinfunction "IN4_5") (pintype "passive"))
      (node (ref "U58") (pin "6") (pinfunction "OUT4_6") (pintype "passive"))
    )
    (net (code "43") (name "HDMI_D2_N") (class "Default")
      (node (ref "CON24") (pin "3") (pinfunction "DAT2-_3") (pintype "passive"))
      (node (ref "U56") (pin "30") (pinfunction "HDMITX2_DN_30") (pintype "passive"))
      (node (ref "U60") (pin "2") (pinfunction "IN2_2") (pintype "passive"))
      (node (ref "U60") (pin "9") (pinfunction "OUT2_9") (pintype "passive"))
    )
    (net (code "44") (name "HDMI_D2_P") (class "Default")
      (node (ref "CON24") (pin "1") (pinfunction "DAT2+_1") (pintype "passive"))
      (node (ref "U56") (pin "31") (pinfunction "HDMITX2_DP_31") (pintype "passive"))
      (node (ref "U60") (pin "1") (pinfunction "IN1_1") (pintype "passive"))
      (node (ref "U60") (pin "10") (pinfunction "OUT1_10") (pintype "passive"))
    )
    (net (code "45") (name "Net-(D21-Anode)") (class "Default")
      (node (ref "D21") (pin "1") (pinfunction "Anode_1") (pintype "passive"))
      (node (ref "R439") (pin "1") (pinfunction "1_1") (pintype "passive"))
    )
    (net (code "46") (name "Net-(D22-Cathode)") (class "Default")
      (node (ref "D22") (pin "2") (pinfunction "Cathode_2") (pintype "passive"))
      (node (ref "R394") (pin "2") (pinfunction "2_2") (pintype "passive"))
      (node (ref "U55") (pin "A5") (pinfunction "~{OE}_A5") (pintype "passive"))
    )
    (net (code "47") (name "Net-(Q14-B)") (class "Default")
      (node (ref "Q14") (pin "1") (pinfunction "B_1") (pintype "passive"))
      (node (ref "R404") (pin "2") (pinfunction "2_2") (pintype "passive"))
    )
    (net (code "48") (name "Net-(Q14-E)") (class "Default")
      (node (ref "Q14") (pin "2") (pinfunction "E_2") (pintype "passive"))
      (node (ref "R405") (pin "1") (pinfunction "1_1") (pintype "passive"))
      (node (ref "R406") (pin "2") (pinfunction "2_2") (pintype "passive"))
    )
    (net (code "49") (name "Net-(U55-SEL)") (class "Default")
      (node (ref "R395") (pin "2") (pinfunction "2_2") (pintype "passive"))
      (node (ref "U55") (pin "A6") (pinfunction "SEL_A6") (pintype "passive"))
    )
    (net (code "50") (name "Net-(U55-VCC)") (class "Default")
      (node (ref "C332") (pin "1") (pinfunction "1_1") (pintype "passive"))
      (node (ref "FB27") (pin "2") (pinfunction "2_2") (pintype "passive"))
      (node (ref "FB28") (pin "2") (pinfunction "2_2") (pintype "passive"))
      (node (ref "R394") (pin "1") (pinfunction "1_1") (pintype "passive"))
      (node (ref "R395") (pin "1") (pinfunction "1_1") (pintype "passive"))
      (node (ref "U55") (pin "A1") (pinfunction "VCC_A1") (pintype "power_in"))
    )
    (net (code "51") (name "Net-(U56-LPF)") (class "Default")
      (node (ref "C333") (pin "1") (pinfunction "1_1") (pintype "passive"))
      (node (ref "U56") (pin "35") (pinfunction "LPF_35") (pintype "passive"))
    )
    (net (code "52") (name "Net-(U56-R6K)") (class "Default")
      (node (ref "R399") (pin "2") (pinfunction "2_2") (pintype "passive"))
      (node (ref "U56") (pin "13") (pinfunction "R6K_13") (pintype "passive"))
    )
    (net (code "53") (name "Net-(U57-A1)") (class "Default")
      (node (ref "R402") (pin "1") (pinfunction "1_1") (pintype "passive"))
      (node (ref "U57") (pin "5") (pinfunction "A1_5") (pintype "passive"))
    )
    (net (code "54") (name "Net-(U57-A2)") (class "Default")
      (node (ref "R403") (pin "1") (pinfunction "1_1") (pintype "passive"))
      (node (ref "U57") (pin "4") (pinfunction "A2_4") (pintype "passive"))
    )
    (net (code "55") (name "VCCA_1V8_HDMIPLL") (class "Default")
      (node (ref "C324") (pin "1") (pinfunction "1_1") (pintype "passive"))
      (node (ref "C325") (pin "1") (pinfunction "1_1") (pintype "passive"))
      (node (ref "C333") (pin "2") (pinfunction "2_2") (pintype "passive"))
      (node (ref "FB25") (pin "2") (pinfunction "2_2") (pintype "passive"))
      (node (ref "U56") (pin "34") (pinfunction "VCCA_HDMIPLL_34") (pintype "power_in"))
    )
    (net (code "56") (name "VCCA_1V8_HDMITX") (class "Default")
      (node (ref "C322") (pin "1") (pinfunction "1_1") (pintype "passive"))
      (node (ref "C323") (pin "1") (pinfunction "1_1") (pintype "passive"))
      (node (ref "FB26") (pin "2") (pinfunction "2_2") (pintype "passive"))
      (node (ref "U56") (pin "26") (pinfunction "VCCA_HDMITX_26") (pintype "power_in"))
    )
    (net (code "57") (name "VCCA_1V8_LVDSPLL") (class "Default")
      (node (ref "C320") (pin "1") (pinfunction "1_1") (pintype "passive"))
      (node (ref "C321") (pin "1") (pinfunction "1_1") (pintype "passive"))
      (node (ref "FB22") (pin "2") (pinfunction "2_2") (pintype "passive"))
      (node (ref "U56") (pin "52") (pinfunction "VCCA_LVDSPLL_52") (pintype "power_in"))
    )
    (net (code "58") (name "VCCA_1V8_LVDSTX") (class "Default")
      (node (ref "C319") (pin "1") (pinfunction "1_1") (pintype "passive"))
      (node (ref "C326") (pin "1") (pinfunction "1_1") (pintype "passive"))
      (node (ref "FB24") (pin "2") (pinfunction "2_2") (pintype "passive"))
      (node (ref "U56") (pin "41") (pinfunction "VCCA_LVDSTX_41") (pintype "power_in"))
    )
    (net (code "59") (name "VCCA_1V8_MIPIRX") (class "Default")
      (node (ref "C312") (pin "1") (pinfunction "1_1") (pintype "passive"))
      (node (ref "C313") (pin "1") (pinfunction "1_1") (pintype "passive"))
      (node (ref "FB21") (pin "2") (pinfunction "2_2") (pintype "passive"))
      (node (ref "U56") (pin "5") (pinfunction "VCCA_MIPIRX_5") (pintype "power_in"))
    )
    (net (code "60") (name "VCCA_1V8_SYSCLK") (class "Default")
      (node (ref "C314") (pin "1") (pinfunction "1_1") (pintype "passive"))
      (node (ref "C315") (pin "1") (pinfunction "1_1") (pintype "passive"))
      (node (ref "FB23") (pin "2") (pinfunction "2_2") (pintype "passive"))
      (node (ref "U56") (pin "50") (pinfunction "VCCA_SYSCLK_50") (pintype "power_in"))
    )
    (net (code "61") (name "VDD_1V8") (class "Default")
      (node (ref "C308") (pin "1") (pinfunction "1_1") (pintype "passive"))
      (node (ref "C309") (pin "1") (pinfunction "1_1") (pintype "passive"))
      (node (ref "C310") (pin "1") (pinfunction "1_1") (pintype "passive"))
      (node (ref "C311") (pin "1") (pinfunction "1_1") (pintype "passive"))
      (node (ref "FB20") (pin "2") (pinfunction "2_2") (pintype "passive"))
      (node (ref "FB28") (pin "1") (pinfunction "1_1") (pintype "passive"))
      (node (ref "R392") (pin "2") (pinfunction "2_2") (pintype "passive"))
      (node (ref "U56") (pin "18") (pinfunction "VDD_18") (pintype "power_in"))
      (node (ref "U56") (pin "33") (pinfunction "VDD_33") (pintype "power_in"))
      (node (ref "U56") (pin "57") (pinfunction "VDD_57") (pintype "power_in"))
    )
    (net (code "62") (name "VDD_1V8_MAIN") (class "Default")
      (node (ref "C316") (pin "1") (pinfunction "1_1") (pintype "passive"))
      (node (ref "C317") (pin "1") (pinfunction "1_1") (pintype "passive"))
      (node (ref "C318") (pin "1") (pinfunction "1_1") (pintype "passive"))
      (node (ref "C329") (pin "1") (pinfunction "1_1") (pintype "passive"))
      (node (ref "FB20") (pin "1") (pinfunction "1_1") (pintype "passive"))
      (node (ref "FB21") (pin "1") (pinfunction "1_1") (pintype "passive"))
      (node (ref "FB22") (pin "1") (pinfunction "1_1") (pintype "passive"))
      (node (ref "FB23") (pin "1") (pinfunction "1_1") (pintype "passive"))
      (node (ref "FB24") (pin "1") (pinfunction "1_1") (pintype "passive"))
      (node (ref "FB25") (pin "1") (pinfunction "1_1") (pintype "passive"))
      (node (ref "FB26") (pin "1") (pinfunction "1_1") (pintype "passive"))
      (node (ref "Q14") (pin "3") (pinfunction "C_3") (pintype "passive"))
      (node (ref "R390") (pin "2") (pinfunction "2_2") (pintype "passive"))
      (node (ref "R391") (pin "2") (pinfunction "2_2") (pintype "passive"))
      (node (ref "U54") (pin "3") (pinfunction "VCCA_3") (pintype "passive"))
      (node (ref "U54") (pin "6") (pinfunction "OE_6") (pintype "passive"))
    )
    (net (code "63") (name "VDD_3V3_MAIN") (class "Default")
      (node (ref "C331") (pin "1") (pinfunction "1_1") (pintype "passive"))
      (node (ref "C334") (pin "1") (pinfunction "1_1") (pintype "passive"))
      (node (ref "FB27") (pin "1") (pinfunction "1_1") (pintype "passive"))
      (node (ref "U54") (pin "7") (pinfunction "VCCB_7") (pintype "passive"))
      (node (ref "U57") (pin "3") (pinfunction "VCCA_3") (pintype "passive"))
      (node (ref "U57") (pin "6") (pinfunction "OE_6") (pintype "passive"))
    )
    (net (code "64") (name "VDD_5V_HDMICONN") (class "Default")
      (node (ref "C335") (pin "1") (pinfunction "1_1") (pintype "passive"))
      (node (ref "CON24") (pin "18") (pinfunction "+5V_18") (pintype "passive"))
      (node (ref "D20") (pin "1") (pinfunction "Anode_1") (pintype "passive"))
      (node (ref "R400") (pin "2") (pinfunction "2_2") (pintype "passive"))
      (node (ref "R401") (pin "2") (pinfunction "2_2") (pintype "passive"))
      (node (ref "U57") (pin "7") (pinfunction "VCCB_7") (pintype "passive"))
    )
    (net (code "65") (name "VDD_5V_MAIN") (class "Default")
      (node (ref "D20") (pin "2") (pinfunction "Cathode_2") (pintype "passive"))
    )
    (net (code "66") (name "XL9555_P16{slash}MIPI_LCD_RST{slash}HDMI_nRST{slash}3V3") (class "Default")
      (node (ref "R439") (pin "2") (pinfunction "2_2") (pintype "passive"))
    )
    (net (code "67") (name "XL9555_P17{slash}HDMI_EN{slash}3V3") (class "Default")
      (node (ref "D22") (pin "1") (pinfunction "Anode_1") (pintype "passive"))
    )
    (net (code "68") (name "unconnected-(CON24-CEC-Pad13)") (class "Default")
      (node (ref "CON24") (pin "13") (pinfunction "CEC_13") (pintype "passive+no_connect"))
    )
    (net (code "69") (name "unconnected-(CON24-NC-Pad14)") (class "Default")
      (node (ref "CON24") (pin "14") (pinfunction "NC_14") (pintype "passive+no_connect"))
    )
    (net (code "70") (name "unconnected-(U55-CLKAN-PadF3)") (class "Default")
      (node (ref "U55") (pin "F3") (pinfunction "CLKAN_F3") (pintype "passive+no_connect"))
    )
    (net (code "71") (name "unconnected-(U55-CLKAP-PadF4)") (class "Default")
      (node (ref "U55") (pin "F4") (pinfunction "CLKAP_F4") (pintype "passive+no_connect"))
    )
    (net (code "72") (name "unconnected-(U55-DA1N-PadE3)") (class "Default")
      (node (ref "U55") (pin "E3") (pinfunction "DA1N_E3") (pintype "passive+no_connect"))
    )
    (net (code "73") (name "unconnected-(U55-DA1P-PadE4)") (class "Default")
      (node (ref "U55") (pin "E4") (pinfunction "DA1P_E4") (pintype "passive+no_connect"))
    )
    (net (code "74") (name "unconnected-(U55-DA2N-PadD3)") (class "Default")
      (node (ref "U55") (pin "D3") (pinfunction "DA2N_D3") (pintype "passive+no_connect"))
    )
    (net (code "75") (name "unconnected-(U55-DA2P-PadD4)") (class "Default")
      (node (ref "U55") (pin "D4") (pinfunction "DA2P_D4") (pintype "passive+no_connect"))
    )
    (net (code "76") (name "unconnected-(U55-DA3N-PadB3)") (class "Default")
      (node (ref "U55") (pin "B3") (pinfunction "DA3N_B3") (pintype "passive+no_connect"))
    )
    (net (code "77") (name "unconnected-(U55-DA3P-PadB4)") (class "Default")
      (node (ref "U55") (pin "B4") (pinfunction "DA3P_B4") (pintype "passive+no_connect"))
    )
    (net (code "78") (name "unconnected-(U55-DA4N-PadA3)") (class "Default")
      (node (ref "U55") (pin "A3") (pinfunction "DA4N_A3") (pintype "passive+no_connect"))
    )
    (net (code "79") (name "unconnected-(U55-DA4P-PadA4)") (class "Default")
      (node (ref "U55") (pin "A4") (pinfunction "DA4P_A4") (pintype "passive+no_connect"))
    )
    (net (code "80") (name "unconnected-(U55-NC1-PadC3)") (class "Default")
      (node (ref "U55") (pin "C3") (pinfunction "NC1_C3") (pintype "passive+no_connect"))
    )
    (net (code "81") (name "unconnected-(U55-NC2-PadC4)") (class "Default")
      (node (ref "U55") (pin "C4") (pinfunction "NC2_C4") (pintype "passive+no_connect"))
    )
    (net (code "82") (name "unconnected-(U56-INT-Pad63)") (class "Default")
      (node (ref "U56") (pin "63") (pinfunction "INT_63") (pintype "passive+no_connect"))
    )
    (net (code "83") (name "unconnected-(U56-LVDSTX0_DN-Pad48)") (class "Default")
      (node (ref "U56") (pin "48") (pinfunction "LVDSTX0_DN_48") (pintype "passive+no_connect"))
    )
    (net (code "84") (name "unconnected-(U56-LVDSTX0_DP-Pad47)") (class "Default")
      (node (ref "U56") (pin "47") (pinfunction "LVDSTX0_DP_47") (pintype "passive+no_connect"))
    )
    (net (code "85") (name "unconnected-(U56-LVDSTX1_DN-Pad46)") (class "Default")
      (node (ref "U56") (pin "46") (pinfunction "LVDSTX1_DN_46") (pintype "passive+no_connect"))
    )
    (net (code "86") (name "unconnected-(U56-LVDSTX1_DP-Pad45)") (class "Default")
      (node (ref "U56") (pin "45") (pinfunction "LVDSTX1_DP_45") (pintype "passive+no_connect"))
    )
    (net (code "87") (name "unconnected-(U56-LVDSTX2_DN-Pad44)") (class "Default")
      (node (ref "U56") (pin "44") (pinfunction "LVDSTX2_DN_44") (pintype "passive+no_connect"))
    )
    (net (code "88") (name "unconnected-(U56-LVDSTX2_DP-Pad43)") (class "Default")
      (node (ref "U56") (pin "43") (pinfunction "LVDSTX2_DP_43") (pintype "passive+no_connect"))
    )
    (net (code "89") (name "unconnected-(U56-LVDSTX3_DN-Pad38)") (class "Default")
      (node (ref "U56") (pin "38") (pinfunction "LVDSTX3_DN_38") (pintype "passive+no_connect"))
    )
    (net (code "90") (name "unconnected-(U56-LVDSTX3_DP-Pad37)") (class "Default")
      (node (ref "U56") (pin "37") (pinfunction "LVDSTX3_DP_37") (pintype "passive+no_connect"))
    )
    (net (code "91") (name "unconnected-(U56-LVDSTX_CKN-Pad40)") (class "Default")
      (node (ref "U56") (pin "40") (pinfunction "LVDSTX_CKN_40") (pintype "passive+no_connect"))
    )
    (net (code "92") (name "unconnected-(U56-LVDSTX_CKP-Pad39)") (class "Default")
      (node (ref "U56") (pin "39") (pinfunction "LVDSTX_CKP_39") (pintype "passive+no_connect"))
    )
    (net (code "93") (name "unconnected-(U56-SCLK_I-Pad60)") (class "Default")
      (node (ref "U56") (pin "60") (pinfunction "SCLK_I_60") (pintype "passive+no_connect"))
    )
    (net (code "94") (name "unconnected-(U56-SD0_CEC-Pad58)") (class "Default")
      (node (ref "U56") (pin "58") (pinfunction "SD0_CEC_58") (pintype "passive+no_connect"))
    )
    (net (code "95") (name "unconnected-(U56-USB_DM-Pad20)") (class "Default")
      (node (ref "U56") (pin "20") (pinfunction "USB_DM_20") (pintype "passive+no_connect"))
    )
    (net (code "96") (name "unconnected-(U56-USB_DP-Pad19)") (class "Default")
      (node (ref "U56") (pin "19") (pinfunction "USB_DP_19") (pintype "passive+no_connect"))
    )
    (net (code "97") (name "unconnected-(U56-USB_ID-Pad16)") (class "Default")
      (node (ref "U56") (pin "16") (pinfunction "USB_ID_16") (pintype "passive+no_connect"))
    )
    (net (code "98") (name "unconnected-(U56-VBUS-Pad15)") (class "Default")
      (node (ref "U56") (pin "15") (pinfunction "VBUS_15") (pintype "passive+no_connect"))
    )
    (net (code "99") (name "unconnected-(U56-WS_I{slash}SPDIF_IN-Pad59)") (class "Default")
      (node (ref "U56") (pin "59") (pinfunction "WS_I/SPDIF_IN_59") (pintype "passive+no_connect"))
    )
    (net (code "100") (name "unconnected-(U59-IN4-Pad5)") (class "Default")
      (node (ref "U59") (pin "5") (pinfunction "IN4_5") (pintype "passive+no_connect"))
    )
    (net (code "101") (name "unconnected-(U59-OUT4-Pad6)") (class "Default")
      (node (ref "U59") (pin "6") (pinfunction "OUT4_6") (pintype "passive+no_connect"))
    )
  )
)
